# Power_Supply.net
KiCad netlist of a schematic drawn in Altium Designer
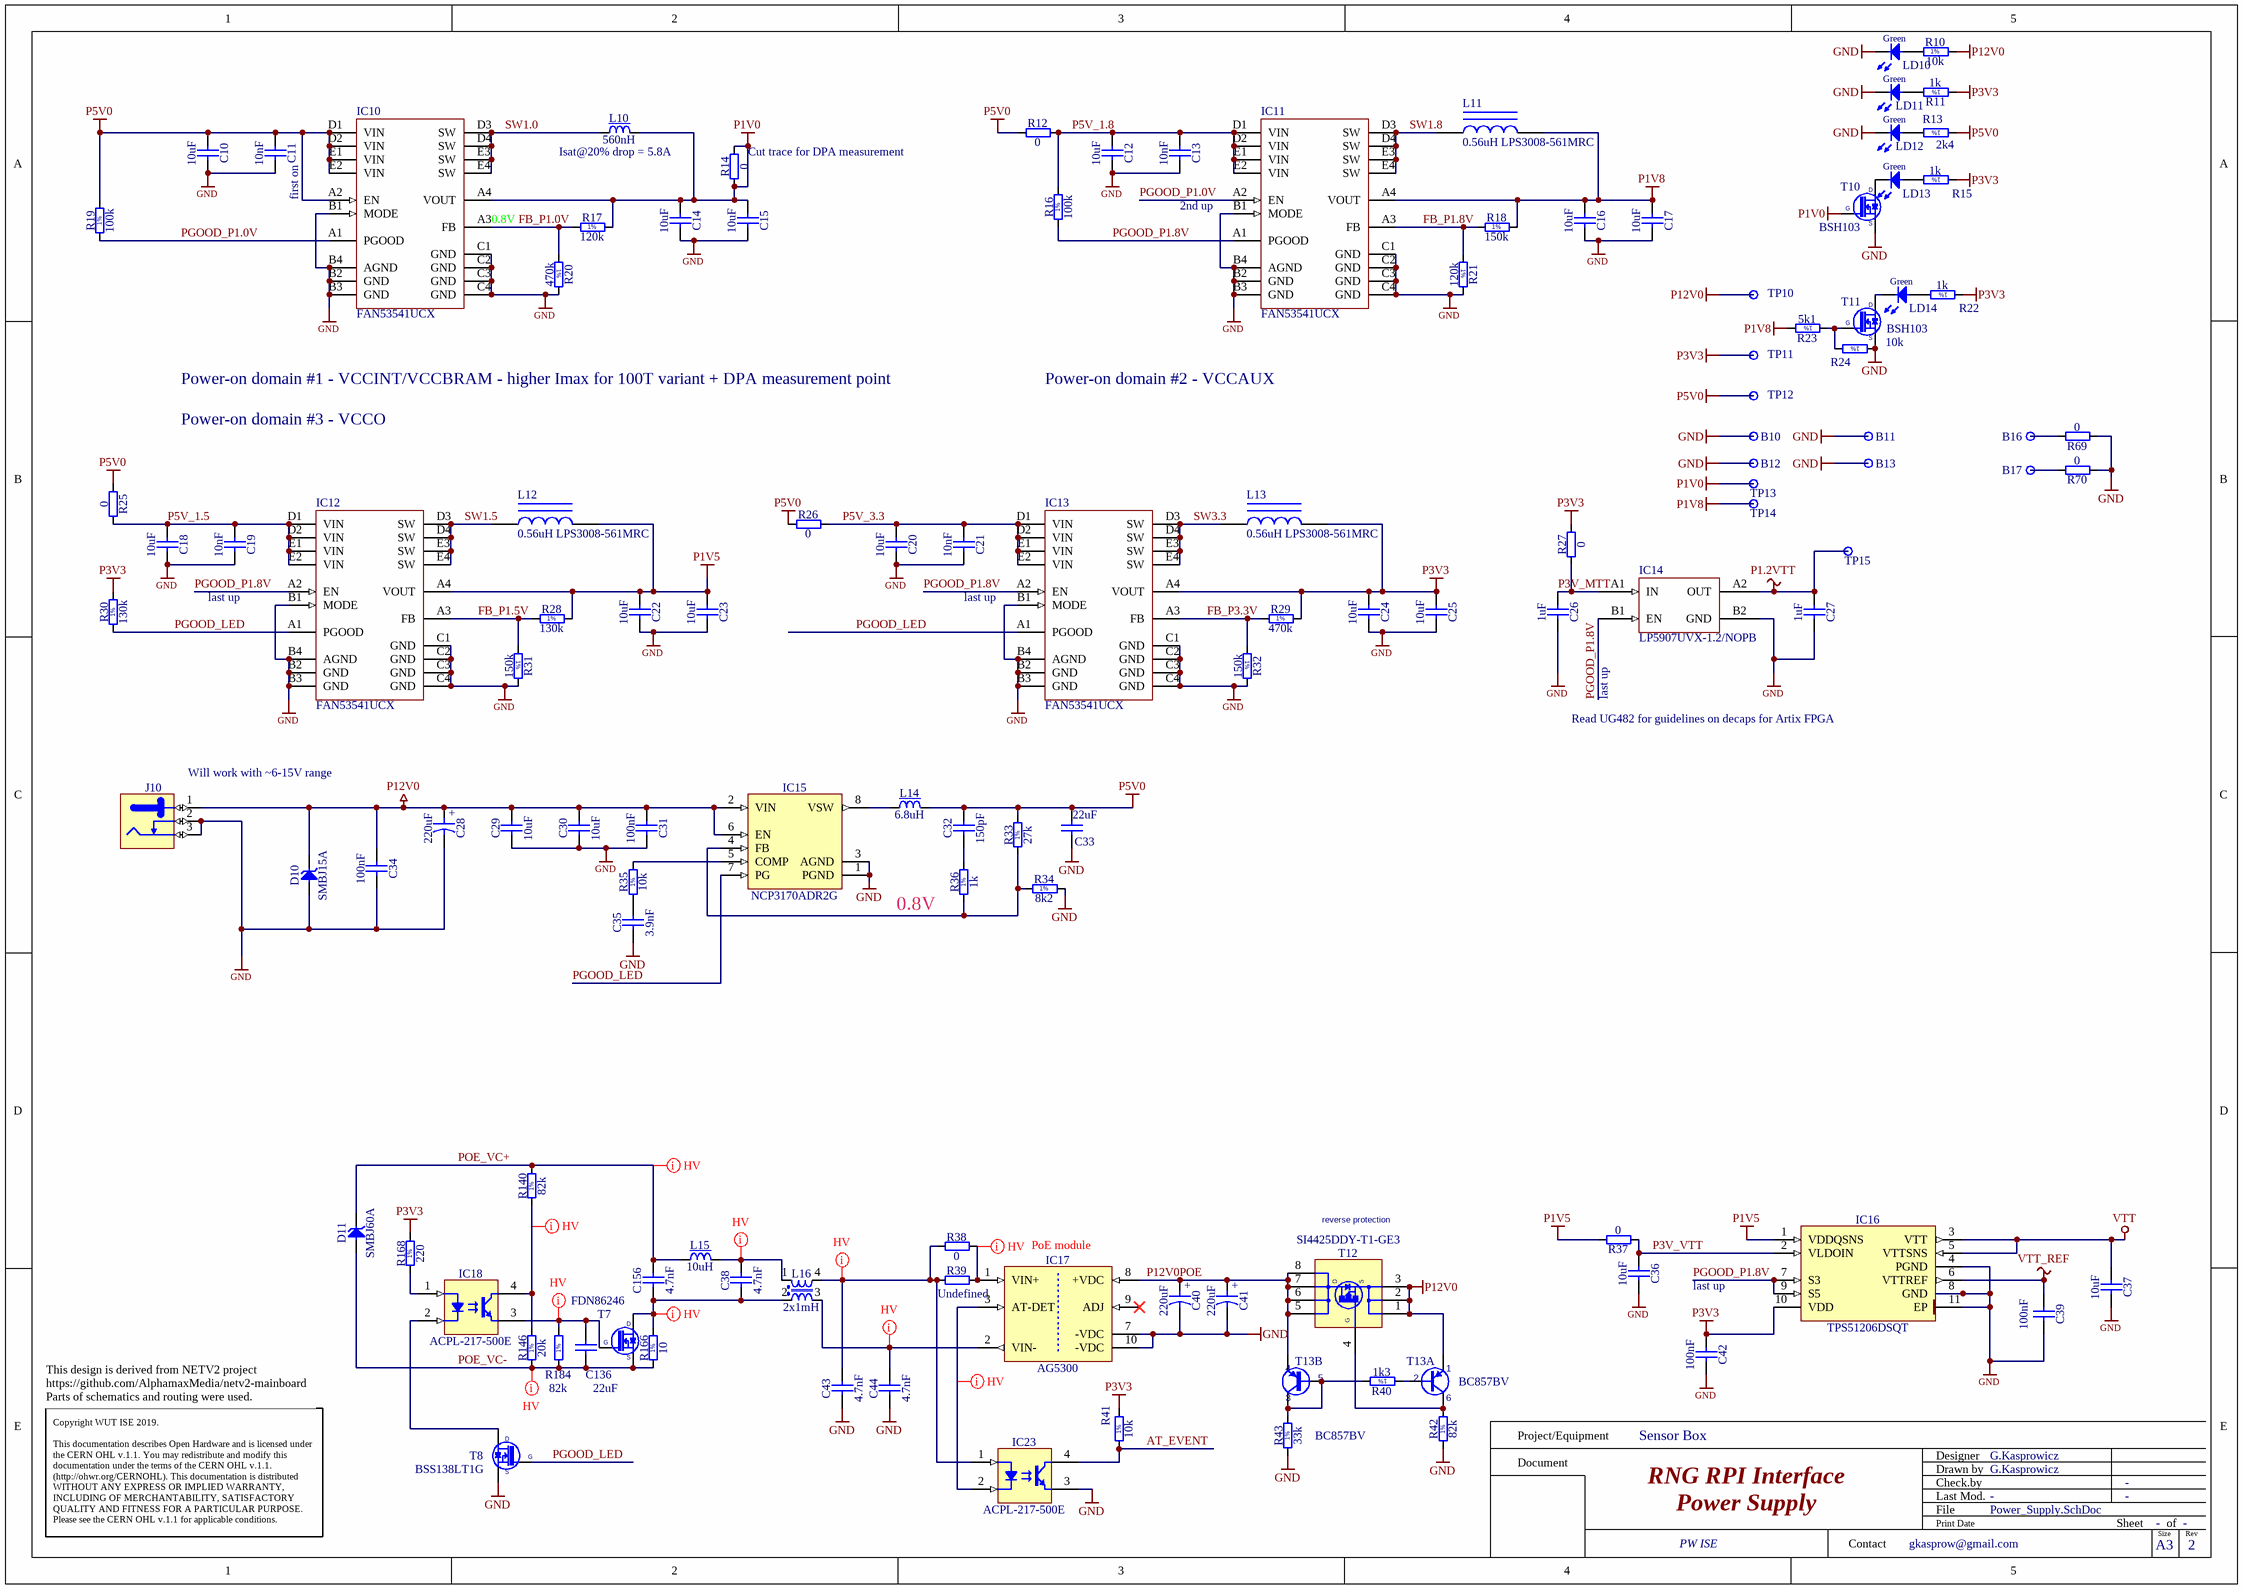
[diagram p0: Power_Supply.SchDoc]

(export (version "E")
  (design (tool "Eeschema 10.0.6"))
  (components
    (comp (ref "B10")
      (value "Plated Hole")
      (footprint "c130h60")
      (description "Single Terminal Socket")
      (fields (field (name "PART NUMBER") "PLATED_HOLE0.6_PAD1.3") (field (name "AUTHOR") "CERN DEM MR"))
      (libsource (lib "Eletro-mechanical") (part "Single Terminal Socket"))
    )
    (comp (ref "B11")
      (value "Plated Hole")
      (footprint "c130h60")
      (description "Single Terminal Socket")
      (fields (field (name "PART NUMBER") "PLATED_HOLE0.6_PAD1.3") (field (name "AUTHOR") "CERN DEM MR"))
      (libsource (lib "Eletro-mechanical") (part "Single Terminal Socket"))
    )
    (comp (ref "B12")
      (value "Plated Hole")
      (footprint "c130h60")
      (description "Single Terminal Socket")
      (fields (field (name "PART NUMBER") "PLATED_HOLE0.6_PAD1.3") (field (name "AUTHOR") "CERN DEM MR"))
      (libsource (lib "Eletro-mechanical") (part "Single Terminal Socket"))
    )
    (comp (ref "B13")
      (value "Plated Hole")
      (footprint "c130h60")
      (description "Single Terminal Socket")
      (fields (field (name "PART NUMBER") "PLATED_HOLE0.6_PAD1.3") (field (name "AUTHOR") "CERN DEM MR"))
      (libsource (lib "Eletro-mechanical") (part "Single Terminal Socket"))
    )
    (comp (ref "B16")
      (value "Plated Hole")
      (footprint "MTG270_500")
      (description "Single Terminal Socket")
      (fields (field (name "PART NUMBER") "PLATED_HOLE2.7_PAD5.0") (field (name "AUTHOR") "CERN DEM JMW"))
      (libsource (lib "Eletro-mechanical") (part "Single Terminal Socket"))
    )
    (comp (ref "B17")
      (value "Plated Hole")
      (footprint "MTG270_500")
      (description "Single Terminal Socket")
      (fields (field (name "PART NUMBER") "PLATED_HOLE2.7_PAD5.0") (field (name "AUTHOR") "CERN DEM JMW"))
      (libsource (lib "Eletro-mechanical") (part "Single Terminal Socket"))
    )
    (comp (ref "C10")
      (value "10uF")
      (footprint "CAPC1608X80N")
      (description "Non-polarised capacitor")
      (fields
        (field (name "PART NUMBER") "CC0603_10UF_10V_10%_X5R")
        (field (name "VOLTAGE") "10V")
        (field (name "AUTHOR") "CERN DEM JLC")
      )
      (libsource (lib "Capacitors") (part "Capacitor - non polarized"))
    )
    (comp (ref "C11")
      (value "10nF")
      (footprint "CAPC1005X55N")
      (description "Non-polarised capacitor")
      (fields
        (field (name "PART NUMBER") "CC0402_10NF_16V_10%_X7R")
        (field (name "VOLTAGE") "16V")
        (field (name "AUTHOR") "CERN DEM JLC")
      )
      (libsource (lib "Capacitors") (part "Capacitor - non polarized"))
    )
    (comp (ref "C12")
      (value "10uF")
      (footprint "CAPC1608X80N")
      (description "Non-polarised capacitor")
      (fields
        (field (name "PART NUMBER") "CC0603_10UF_10V_10%_X5R")
        (field (name "VOLTAGE") "10V")
        (field (name "AUTHOR") "CERN DEM JLC")
      )
      (libsource (lib "Capacitors") (part "Capacitor - non polarized"))
    )
    (comp (ref "C13")
      (value "10nF")
      (footprint "CAPC1005X55N")
      (description "Non-polarised capacitor")
      (fields
        (field (name "PART NUMBER") "CC0402_10NF_16V_10%_X7R")
        (field (name "VOLTAGE") "16V")
        (field (name "AUTHOR") "CERN DEM JLC")
      )
      (libsource (lib "Capacitors") (part "Capacitor - non polarized"))
    )
    (comp (ref "C14")
      (value "10uF")
      (footprint "CAPC1608X80N")
      (description "Non-polarised capacitor")
      (fields
        (field (name "PART NUMBER") "CC0603_10UF_10V_10%_X5R")
        (field (name "VOLTAGE") "10V")
        (field (name "AUTHOR") "CERN DEM JLC")
      )
      (libsource (lib "Capacitors") (part "Capacitor - non polarized"))
    )
    (comp (ref "C15")
      (value "10uF")
      (footprint "CAPC1608X80N")
      (description "Non-polarised capacitor")
      (fields
        (field (name "PART NUMBER") "CC0603_10UF_10V_10%_X5R")
        (field (name "VOLTAGE") "10V")
        (field (name "AUTHOR") "CERN DEM JLC")
      )
      (libsource (lib "Capacitors") (part "Capacitor - non polarized"))
    )
    (comp (ref "C16")
      (value "10uF")
      (footprint "CAPC1608X80N")
      (description "Non-polarised capacitor")
      (fields
        (field (name "PART NUMBER") "CC0603_10UF_10V_10%_X5R")
        (field (name "VOLTAGE") "10V")
        (field (name "AUTHOR") "CERN DEM JLC")
      )
      (libsource (lib "Capacitors") (part "Capacitor - non polarized"))
    )
    (comp (ref "C17")
      (value "10uF")
      (footprint "CAPC1608X80N")
      (description "Non-polarised capacitor")
      (fields
        (field (name "PART NUMBER") "CC0603_10UF_10V_10%_X5R")
        (field (name "VOLTAGE") "10V")
        (field (name "AUTHOR") "CERN DEM JLC")
      )
      (libsource (lib "Capacitors") (part "Capacitor - non polarized"))
    )
    (comp (ref "C18")
      (value "10uF")
      (footprint "CAPC1608X80N")
      (description "Non-polarised capacitor")
      (fields
        (field (name "PART NUMBER") "CC0603_10UF_10V_10%_X5R")
        (field (name "VOLTAGE") "10V")
        (field (name "AUTHOR") "CERN DEM JLC")
      )
      (libsource (lib "Capacitors") (part "Capacitor - non polarized"))
    )
    (comp (ref "C19")
      (value "10nF")
      (footprint "CAPC1005X55N")
      (description "Non-polarised capacitor")
      (fields
        (field (name "PART NUMBER") "CC0402_10NF_16V_10%_X7R")
        (field (name "VOLTAGE") "16V")
        (field (name "AUTHOR") "CERN DEM JLC")
      )
      (libsource (lib "Capacitors") (part "Capacitor - non polarized"))
    )
    (comp (ref "C20")
      (value "10uF")
      (footprint "CAPC1608X80N")
      (description "Non-polarised capacitor")
      (fields
        (field (name "PART NUMBER") "CC0603_10UF_10V_10%_X5R")
        (field (name "VOLTAGE") "10V")
        (field (name "AUTHOR") "CERN DEM JLC")
      )
      (libsource (lib "Capacitors") (part "Capacitor - non polarized"))
    )
    (comp (ref "C21")
      (value "10nF")
      (footprint "CAPC1005X55N")
      (description "Non-polarised capacitor")
      (fields
        (field (name "PART NUMBER") "CC0402_10NF_16V_10%_X7R")
        (field (name "VOLTAGE") "16V")
        (field (name "AUTHOR") "CERN DEM JLC")
      )
      (libsource (lib "Capacitors") (part "Capacitor - non polarized"))
    )
    (comp (ref "C22")
      (value "10uF")
      (footprint "CAPC1608X80N")
      (description "Non-polarised capacitor")
      (fields
        (field (name "PART NUMBER") "CC0603_10UF_10V_10%_X5R")
        (field (name "VOLTAGE") "10V")
        (field (name "AUTHOR") "CERN DEM JLC")
      )
      (libsource (lib "Capacitors") (part "Capacitor - non polarized"))
    )
    (comp (ref "C23")
      (value "10uF")
      (footprint "CAPC1608X80N")
      (description "Non-polarised capacitor")
      (fields
        (field (name "PART NUMBER") "CC0603_10UF_10V_10%_X5R")
        (field (name "VOLTAGE") "10V")
        (field (name "AUTHOR") "CERN DEM JLC")
      )
      (libsource (lib "Capacitors") (part "Capacitor - non polarized"))
    )
    (comp (ref "C24")
      (value "10uF")
      (footprint "CAPC1608X80N")
      (description "Non-polarised capacitor")
      (fields
        (field (name "PART NUMBER") "CC0603_10UF_10V_10%_X5R")
        (field (name "VOLTAGE") "10V")
        (field (name "AUTHOR") "CERN DEM JLC")
      )
      (libsource (lib "Capacitors") (part "Capacitor - non polarized"))
    )
    (comp (ref "C25")
      (value "10uF")
      (footprint "CAPC1608X80N")
      (description "Non-polarised capacitor")
      (fields
        (field (name "PART NUMBER") "CC0603_10UF_10V_10%_X5R")
        (field (name "VOLTAGE") "10V")
        (field (name "AUTHOR") "CERN DEM JLC")
      )
      (libsource (lib "Capacitors") (part "Capacitor - non polarized"))
    )
    (comp (ref "C26")
      (value "1uF")
      (footprint "CAPC1005X55N")
      (description "Non-polarised capacitor")
      (fields
        (field (name "PART NUMBER") "CC0402_1UF_16V_10%_X5R")
        (field (name "VOLTAGE") "16V")
        (field (name "AUTHOR") "CERN DEM JLC")
      )
      (libsource (lib "Capacitors") (part "Capacitor - non polarized"))
    )
    (comp (ref "C27")
      (value "1uF")
      (footprint "CAPC1005X55N")
      (description "Non-polarised capacitor")
      (fields
        (field (name "PART NUMBER") "CC0402_1UF_16V_10%_X5R")
        (field (name "VOLTAGE") "16V")
        (field (name "AUTHOR") "CERN DEM JLC")
      )
      (libsource (lib "Capacitors") (part "Capacitor - non polarized"))
    )
    (comp (ref "C28")
      (value "220uF")
      (footprint "CAPAE830X620N")
      (description "Polarised capacitor")
      (fields
        (field (name "PART NUMBER") "CAE830-620_220UF_16V_20%")
        (field (name "VOLTAGE") "16V")
        (field (name "AUTHOR") "CERN DEM JLC")
      )
      (libsource (lib "Capacitors") (part "Capacitor - polarized"))
    )
    (comp (ref "C29")
      (value "10uF")
      (footprint "CAPC3216X180N")
      (description "Non-polarised capacitor")
      (fields
        (field (name "PART NUMBER") "CC1206_10UF_25V_10%_X7R")
        (field (name "VOLTAGE") "25V")
        (field (name "AUTHOR") "CERN DEM JLC")
      )
      (libsource (lib "Capacitors") (part "Capacitor - non polarized"))
    )
    (comp (ref "C30")
      (value "10uF")
      (footprint "CAPC3216X180N")
      (description "Non-polarised capacitor")
      (fields
        (field (name "PART NUMBER") "CC1206_10UF_25V_10%_X7R")
        (field (name "VOLTAGE") "25V")
        (field (name "AUTHOR") "CERN DEM JLC")
      )
      (libsource (lib "Capacitors") (part "Capacitor - non polarized"))
    )
    (comp (ref "C31")
      (value "100nF")
      (footprint "CAPC2012X135N")
      (description "Non-polarised capacitor")
      (fields
        (field (name "PART NUMBER") "CC0805_100NF_50V_10%_X7R")
        (field (name "VOLTAGE") "50V")
        (field (name "AUTHOR") "CERN DEM JLC")
      )
      (libsource (lib "Capacitors") (part "Capacitor - non polarized"))
    )
    (comp (ref "C32")
      (value "150pF")
      (footprint "CAPC1608X87N")
      (description "Non-polarised capacitor")
      (fields
        (field (name "PART NUMBER") "CC0603_150PF_50V_1%_NP0")
        (field (name "VOLTAGE") "50V")
        (field (name "AUTHOR") "CERN DEM MR")
      )
      (libsource (lib "Capacitors") (part "Capacitor - non polarized"))
    )
    (comp (ref "C33")
      (value "22uF")
      (footprint "CAPC2012X135N")
      (description "Non-polarised capacitor")
      (fields
        (field (name "PART NUMBER") "CC0805_22UF_16V_10%_X5R")
        (field (name "VOLTAGE") "16V")
        (field (name "AUTHOR") "CERN DEM JLC")
      )
      (libsource (lib "Capacitors") (part "Capacitor - non polarized"))
    )
    (comp (ref "C34")
      (value "100nF")
      (footprint "CAPC2012X135N")
      (description "Non-polarised capacitor")
      (fields
        (field (name "PART NUMBER") "CC0805_100NF_50V_10%_X7R")
        (field (name "VOLTAGE") "50V")
        (field (name "AUTHOR") "CERN DEM JLC")
      )
      (libsource (lib "Capacitors") (part "Capacitor - non polarized"))
    )
    (comp (ref "C35")
      (value "3.9nF")
      (footprint "CAPC1608X87N")
      (description "Non-polarised capacitor")
      (fields
        (field (name "PART NUMBER") "CC0603_3.9NF_50V_5%_X7R")
        (field (name "VOLTAGE") "50V")
        (field (name "AUTHOR") "CERN DEM JLC")
      )
      (libsource (lib "Capacitors") (part "Capacitor - non polarized"))
    )
    (comp (ref "C36")
      (value "10uF")
      (footprint "CAPC1608X80N")
      (description "Non-polarised capacitor")
      (fields
        (field (name "PART NUMBER") "CC0603_10UF_10V_10%_X5R")
        (field (name "VOLTAGE") "10V")
        (field (name "AUTHOR") "CERN DEM JLC")
      )
      (libsource (lib "Capacitors") (part "Capacitor - non polarized"))
    )
    (comp (ref "C37")
      (value "10uF")
      (footprint "CAPC1608X80N")
      (description "Non-polarised capacitor")
      (fields
        (field (name "PART NUMBER") "CC0603_10UF_10V_10%_X5R")
        (field (name "VOLTAGE") "10V")
        (field (name "AUTHOR") "CERN DEM JLC")
      )
      (libsource (lib "Capacitors") (part "Capacitor - non polarized"))
    )
    (comp (ref "C38")
      (value "4.7nF")
      (footprint "CAPC3216X140N")
      (description "Non-polarised capacitor")
      (fields
        (field (name "PART NUMBER") "CC1206_4.7NF_500V_10%_X7R")
        (field (name "VOLTAGE") "500V")
        (field (name "AUTHOR") "GK")
      )
      (libsource (lib "LIBRARY_SCH") (part "CAP_SMD_1206_4.7n_500V"))
    )
    (comp (ref "C39")
      (value "100nF")
      (footprint "CAPC0603X33N")
      (description "Non-polarised capacitor")
      (fields
        (field (name "PART NUMBER") "CC0201_100NF_6.3V_10%_X5R")
        (field (name "VOLTAGE") "6.3V")
        (field (name "AUTHOR") "CERN DEM JLC")
      )
      (libsource (lib "Capacitors") (part "Capacitor - non polarized"))
    )
    (comp (ref "C40")
      (value "220uF")
      (footprint "CAPAE830X620N")
      (description "Polarised capacitor")
      (fields
        (field (name "PART NUMBER") "CAE830-620_220UF_16V_20%")
        (field (name "VOLTAGE") "16V")
        (field (name "AUTHOR") "CERN DEM JLC")
      )
      (libsource (lib "Capacitors") (part "Capacitor - polarized"))
    )
    (comp (ref "C41")
      (value "220uF")
      (footprint "CAPAE830X620N")
      (description "Polarised capacitor")
      (fields
        (field (name "PART NUMBER") "CAE830-620_220UF_16V_20%")
        (field (name "VOLTAGE") "16V")
        (field (name "AUTHOR") "CERN DEM JLC")
      )
      (libsource (lib "Capacitors") (part "Capacitor - polarized"))
    )
    (comp (ref "C42")
      (value "100nF")
      (footprint "CAPC0603X33N")
      (description "Non-polarised capacitor")
      (fields
        (field (name "PART NUMBER") "CC0201_100NF_6.3V_10%_X5R")
        (field (name "VOLTAGE") "6.3V")
        (field (name "AUTHOR") "CERN DEM JLC")
      )
      (libsource (lib "Capacitors") (part "Capacitor - non polarized"))
    )
    (comp (ref "C43")
      (value "4.7nF")
      (footprint "CAPC3216X140N")
      (description "Non-polarised capacitor")
      (fields
        (field (name "PART NUMBER") "CC1206_4.7NF_500V_10%_X7R")
        (field (name "VOLTAGE") "500V")
        (field (name "AUTHOR") "GK")
      )
      (libsource (lib "LIBRARY_SCH") (part "CAP_SMD_1206_4.7n_500V"))
    )
    (comp (ref "C44")
      (value "4.7nF")
      (footprint "CAPC3216X140N")
      (description "Non-polarised capacitor")
      (fields
        (field (name "PART NUMBER") "CC1206_4.7NF_500V_10%_X7R")
        (field (name "VOLTAGE") "500V")
        (field (name "AUTHOR") "GK")
      )
      (libsource (lib "LIBRARY_SCH") (part "CAP_SMD_1206_4.7n_500V"))
    )
    (comp (ref "C136")
      (value "22uF")
      (footprint "CAPC2012X135N")
      (description "Non-polarised capacitor")
      (fields
        (field (name "PART NUMBER") "CC0805_22UF_16V_10%_X5R")
        (field (name "VOLTAGE") "16V")
        (field (name "AUTHOR") "CERN DEM JLC")
      )
      (libsource (lib "Capacitors") (part "Capacitor - non polarized"))
    )
    (comp (ref "C156")
      (value "4.7nF")
      (footprint "CAPC3216X140N")
      (description "Non-polarised capacitor")
      (fields
        (field (name "PART NUMBER") "CC1206_4.7NF_500V_10%_X7R")
        (field (name "VOLTAGE") "500V")
        (field (name "AUTHOR") "GK")
      )
      (libsource (lib "LIBRARY_SCH") (part "CAP_SMD_1206_4.7n_500V"))
    )
    (comp (ref "D10")
      (value "SMBJ15A")
      (footprint "DIOM5336X265N")
      (description "Zener Diode")
      (fields
        (field (name "VOLTAGE") "15V")
        (field (name "POWER") "600W")
        (field (name "AUTHOR") "CERN DEM JLC")
      )
      (libsource (lib "ICs And Semiconductors") (part "Diode Zener"))
    )
    (comp (ref "D11")
      (value "SMBJ60A")
      (footprint "DIOM5336X265N")
      (description "Zener Diode")
      (fields
        (field (name "VOLTAGE") "60V")
        (field (name "POWER") "600W")
        (field (name "AUTHOR") "CERN DEM JLC")
      )
      (libsource (lib "ICs And Semiconductors") (part "Diode Zener"))
    )
    (comp (ref "IC10")
      (value "FAN53541UCX")
      (footprint "BGA20C40P4X5_156X196X62")
      (description "2.4MHz, 5A TinyBuck Synchronous Buck Regulator")
      (libsource (lib "commonsch-new") (part "FAN53541UCX"))
    )
    (comp (ref "IC11")
      (value "FAN53541UCX")
      (footprint "BGA20C40P4X5_156X196X62")
      (description "2.4MHz, 5A TinyBuck Synchronous Buck Regulator")
      (libsource (lib "commonsch-new") (part "FAN53541UCX"))
    )
    (comp (ref "IC12")
      (value "FAN53541UCX")
      (footprint "BGA20C40P4X5_156X196X62")
      (description "2.4MHz, 5A TinyBuck Synchronous Buck Regulator")
      (libsource (lib "commonsch-new") (part "FAN53541UCX"))
    )
    (comp (ref "IC13")
      (value "FAN53541UCX")
      (footprint "BGA20C40P4X5_156X196X62")
      (description "2.4MHz, 5A TinyBuck Synchronous Buck Regulator")
      (libsource (lib "commonsch-new") (part "FAN53541UCX"))
    )
    (comp (ref "IC14")
      (value "LP5907UVX-1.2/NOPB")
      (footprint "TI_YKE004")
      (description "Ultra low-noise 250mA LDO for RF and analog in DSBGA")
      (libsource (lib "commonsch-new") (part "LP5907UVX"))
    )
    (comp (ref "IC15")
      (value "NCP3170ADR2G")
      (footprint "SOIC127P600X175-8N")
      (description "Synchronous PWM Switching Converter")
      (fields (field (name "MANUFACTURER") "ON SEMICONDUCTOR") (field (name "AUTHOR") "CERN DEM MR"))
      (libsource (lib "ICs And Semiconductors") (part "NCP3170ADR2G"))
    )
    (comp (ref "IC16")
      (value "TPS51206DSQT")
      (footprint "SON40P200X200X80-11N-R100X160")
      (fields (field (name "MANUFACTURER") "TEXAS INSTRUMENTS") (field (name "AUTHOR") "CERN DEM JLC"))
      (libsource (lib "ICs And Semiconductors") (part "TPS51206"))
    )
    (comp (ref "IC17")
      (value "AG5300")
      (footprint "SILVERTEL_AG5300")
      (description "Power-over-Ethernet Plus (POE+) Module")
      (fields (field (name "MANUFACTURER") "SILVERTEL") (field (name "AUTHOR") "CERN DEM JLC"))
      (libsource (lib "ICs And Semiconductors") (part "AG5300"))
    )
    (comp (ref "IC18")
      (value "ACPL-217-500E")
      (footprint "SOIC127P700X242-4N")
      (description "Single Optocoupler")
      (fields (field (name "MANUFACTURER") "AVAGO TECHNOLOGIES") (field (name "AUTHOR") "CERN DEM JLC"))
      (libsource (lib "ICs And Semiconductors") (part "Optocoupler Type7"))
    )
    (comp (ref "IC23")
      (value "ACPL-217-500E")
      (footprint "SOIC127P700X242-4N")
      (description "Single Optocoupler")
      (fields (field (name "MANUFACTURER") "AVAGO TECHNOLOGIES") (field (name "AUTHOR") "CERN DEM JLC"))
      (libsource (lib "ICs And Semiconductors") (part "Optocoupler Type7"))
    )
    (comp (ref "J10")
      (value "Jack")
      (footprint "CLIFF_FC68148(DC-10A)")
      (description "12V /  5A, 2.1mm Diameter Pin, DC Power Socket With  Switch. DC10A Type")
      (fields
        (field (name "PART NUMBER") "CLIFF_FC68148(DC-10A)")
        (field (name "MANUFACTURER") "CLIFF ELECTRONIC COMPONENTS")
        (field (name "AUTHOR") "CERN DEM JLC")
      )
      (libsource (lib "Connectors") (part "CLIFF_FC68148(DC-10A)"))
    )
    (comp (ref "L10")
      (value "560nH")
      (footprint "IND_COILCRAFT_XAL5020")
      (description "Inductor With Core")
      (fields
        (field (name "PART NUMBER") "IND_560NH_20%_COILCRAFT_XAL5020")
        (field (name "POWER") "9.9A")
        (field (name "AUTHOR") "CERN DEM MR")
      )
      (libsource (lib "Inductors & Transformers") (part "Inductor With Magnetic core"))
    )
    (comp (ref "L11")
      (value "0.56uH LPS3008-561MRC")
      (footprint "COILCRAFT_LPS3008")
      (description "Magnetic-Core Inductor")
      (fields (field (name "MPN") "LPS3008-561MRC"))
      (libsource (lib "Miscellaneous Devices") (part "Inductor Iron"))
    )
    (comp (ref "L12")
      (value "0.56uH LPS3008-561MRC")
      (footprint "COILCRAFT_LPS3008")
      (description "Magnetic-Core Inductor")
      (fields (field (name "MPN") "LPS3008-561MRC"))
      (libsource (lib "Miscellaneous Devices") (part "Inductor Iron"))
    )
    (comp (ref "L13")
      (value "0.56uH LPS3008-561MRC")
      (footprint "COILCRAFT_LPS3008")
      (description "Magnetic-Core Inductor")
      (fields (field (name "MPN") "LPS3008-561MRC"))
      (libsource (lib "Miscellaneous Devices") (part "Inductor Iron"))
    )
    (comp (ref "L14")
      (value "6.8uH")
      (footprint "INDM6965X300N")
      (description "Inductor With Core")
      (fields
        (field (name "PART NUMBER") "IND2525_6.8UH_20%_VISHAY_IHLP-2525CZ-01")
        (field (name "POWER") "4.5A")
        (field (name "AUTHOR") "CERN DEM MR")
      )
      (libsource (lib "Inductors & Transformers") (part "Inductor With Magnetic core"))
    )
    (comp (ref "L15")
      (value "10uH")
      (footprint "IND_MURATA-PS_8400")
      (description "Inductor With Core")
      (fields
        (field (name "PART NUMBER") "IND_10UH_10%_MURATA-PS_8400")
        (field (name "POWER") "950mA")
        (field (name "AUTHOR") "CERN DEM JLC")
      )
      (libsource (lib "Inductors & Transformers") (part "Inductor With Magnetic core"))
    )
    (comp (ref "L16")
      (value "2x1mH")
      (footprint "IND_WURTH_WE-SL2")
      (description "Inductor Common Mode")
      (fields
        (field (name "PART NUMBER") "IND_1MH_50%_WURTH_WE-SL2-744222")
        (field (name "POWER") "800mA")
        (field (name "AUTHOR") "CERN DEM JLC")
      )
      (libsource (lib "Inductors & Transformers") (part "Inductor Common Mode 1Dot-4 2Dot-3"))
    )
    (comp (ref "LD10")
      (value "Green")
      (footprint "LED_KINGBRIGHT_KPH-1608CGCK")
      (description "LED Green 1C 2A")
      (fields
        (field (name "PART NUMBER") "LED_KINGBRIGHT_KPH-1608CGCK")
        (field (name "MANUFACTURER") "KINGBRIGHT")
        (field (name "AUTHOR") "CERN DEM JLC")
      )
      (libsource (lib "ICs And Semiconductors") (part "LED Green 1C 2A"))
    )
    (comp (ref "LD11")
      (value "Green")
      (footprint "LED_KINGBRIGHT_KPH-1608CGCK")
      (description "LED Green 1C 2A")
      (fields
        (field (name "PART NUMBER") "LED_KINGBRIGHT_KPH-1608CGCK")
        (field (name "MANUFACTURER") "KINGBRIGHT")
        (field (name "AUTHOR") "CERN DEM JLC")
      )
      (libsource (lib "ICs And Semiconductors") (part "LED Green 1C 2A"))
    )
    (comp (ref "LD12")
      (value "Green")
      (footprint "LED_KINGBRIGHT_KPH-1608CGCK")
      (description "LED Green 1C 2A")
      (fields
        (field (name "PART NUMBER") "LED_KINGBRIGHT_KPH-1608CGCK")
        (field (name "MANUFACTURER") "KINGBRIGHT")
        (field (name "AUTHOR") "CERN DEM JLC")
      )
      (libsource (lib "ICs And Semiconductors") (part "LED Green 1C 2A"))
    )
    (comp (ref "LD13")
      (value "Green")
      (footprint "LED_KINGBRIGHT_KPH-1608CGCK")
      (description "LED Green 1C 2A")
      (fields
        (field (name "PART NUMBER") "LED_KINGBRIGHT_KPH-1608CGCK")
        (field (name "MANUFACTURER") "KINGBRIGHT")
        (field (name "AUTHOR") "CERN DEM JLC")
      )
      (libsource (lib "ICs And Semiconductors") (part "LED Green 1C 2A"))
    )
    (comp (ref "LD14")
      (value "Green")
      (footprint "LED_KINGBRIGHT_KPH-1608CGCK")
      (description "LED Green 1C 2A")
      (fields
        (field (name "PART NUMBER") "LED_KINGBRIGHT_KPH-1608CGCK")
        (field (name "MANUFACTURER") "KINGBRIGHT")
        (field (name "AUTHOR") "CERN DEM JLC")
      )
      (libsource (lib "ICs And Semiconductors") (part "LED Green 1C 2A"))
    )
    (comp (ref "R10")
      (value "10k")
      (footprint "RESC1005X40N")
      (description "Resistor - 1%")
      (fields
        (field (name "PART NUMBER") "R0402_10K_1%_0.0625W_100PPM")
        (field (name "POWER") "0.0625W")
        (field (name "AUTHOR") "CERN DEM JLC")
      )
      (libsource (lib "Resistors") (part "Resistor - 1%"))
    )
    (comp (ref "R11")
      (value "1k")
      (footprint "RESC1005X40N")
      (description "Resistor - 1%")
      (fields
        (field (name "PART NUMBER") "R0402_1K_1%_0.0625W_100PPM")
        (field (name "POWER") "0.0625W")
        (field (name "AUTHOR") "CERN DEM JLC")
      )
      (libsource (lib "Resistors") (part "Resistor - 1%"))
    )
    (comp (ref "R12")
      (value "0")
      (footprint "RESC1608X55N")
      (description "Resistor")
      (fields
        (field (name "PART NUMBER") "R0603_0R_JUMPER")
        (field (name "MANUFACTURER") "GENERIC")
        (field (name "AUTHOR") "CERN DEM JLC")
      )
      (libsource (lib "Resistors") (part "Resistor"))
    )
    (comp (ref "R13")
      (value "2k4")
      (footprint "RESC1005X40N")
      (description "Resistor - 1%")
      (fields
        (field (name "PART NUMBER") "R0402_2K4_1%_0.0625W_100PPM")
        (field (name "POWER") "0.0625W")
        (field (name "AUTHOR") "CERN DEM JLC")
      )
      (libsource (lib "Resistors") (part "Resistor - 1%"))
    )
    (comp (ref "R14")
      (value "0")
      (footprint "RESC1608X55N")
      (description "Resistor")
      (fields
        (field (name "PART NUMBER") "R0603_0R_JUMPER")
        (field (name "MANUFACTURER") "GENERIC")
        (field (name "AUTHOR") "CERN DEM JLC")
      )
      (libsource (lib "Resistors") (part "Resistor"))
    )
    (comp (ref "R15")
      (value "1k")
      (footprint "RESC1005X40N")
      (description "Resistor - 1%")
      (fields
        (field (name "PART NUMBER") "R0402_1K_1%_0.0625W_100PPM")
        (field (name "POWER") "0.0625W")
        (field (name "AUTHOR") "CERN DEM JLC")
      )
      (libsource (lib "Resistors") (part "Resistor - 1%"))
    )
    (comp (ref "R16")
      (value "100k")
      (footprint "RESC1005X40N")
      (description "Resistor - 1%")
      (fields
        (field (name "PART NUMBER") "R0402_100K_1%_0.0625W_100PPM")
        (field (name "POWER") "0.0625W")
        (field (name "AUTHOR") "CERN DEM JLC")
      )
      (libsource (lib "Resistors") (part "Resistor - 1%"))
    )
    (comp (ref "R17")
      (value "120k")
      (footprint "RESC1005X40N")
      (description "Resistor - 1%")
      (fields
        (field (name "PART NUMBER") "R0402_120K_1%_0.0625W_100PPM")
        (field (name "POWER") "0.0625W")
        (field (name "AUTHOR") "CERN DEM JLC")
      )
      (libsource (lib "Resistors") (part "Resistor - 1%"))
    )
    (comp (ref "R18")
      (value "150k")
      (footprint "RESC1005X40N")
      (description "Resistor - 1%")
      (fields
        (field (name "PART NUMBER") "R0402_150K_1%_0.0625W_100PPM")
        (field (name "POWER") "0.0625W")
        (field (name "AUTHOR") "CERN DEM JLC")
      )
      (libsource (lib "Resistors") (part "Resistor - 1%"))
    )
    (comp (ref "R19")
      (value "100k")
      (footprint "RESC1005X40N")
      (description "Resistor - 1%")
      (fields
        (field (name "PART NUMBER") "R0402_100K_1%_0.0625W_100PPM")
        (field (name "POWER") "0.0625W")
        (field (name "AUTHOR") "CERN DEM JLC")
      )
      (libsource (lib "Resistors") (part "Resistor - 1%"))
    )
    (comp (ref "R20")
      (value "470k")
      (footprint "RESC1005X40N")
      (description "Resistor - 1%")
      (fields
        (field (name "PART NUMBER") "R0402_470K_1%_0.0625W_100PPM")
        (field (name "POWER") "0.0625W")
        (field (name "AUTHOR") "CERN DEM JLC")
      )
      (libsource (lib "Resistors") (part "Resistor - 1%"))
    )
    (comp (ref "R21")
      (value "120k")
      (footprint "RESC1005X40N")
      (description "Resistor - 1%")
      (fields
        (field (name "PART NUMBER") "R0402_120K_1%_0.0625W_100PPM")
        (field (name "POWER") "0.0625W")
        (field (name "AUTHOR") "CERN DEM JLC")
      )
      (libsource (lib "Resistors") (part "Resistor - 1%"))
    )
    (comp (ref "R22")
      (value "1k")
      (footprint "RESC1005X40N")
      (description "Resistor - 1%")
      (fields
        (field (name "PART NUMBER") "R0402_1K_1%_0.0625W_100PPM")
        (field (name "POWER") "0.0625W")
        (field (name "AUTHOR") "CERN DEM JLC")
      )
      (libsource (lib "Resistors") (part "Resistor - 1%"))
    )
    (comp (ref "R23")
      (value "5k1")
      (footprint "RESC1005X40N")
      (description "Resistor - 1%")
      (fields
        (field (name "PART NUMBER") "R0402_5K1_1%_0.0625W_100PPM")
        (field (name "POWER") "0.0625W")
        (field (name "AUTHOR") "CERN DEM JLC")
      )
      (libsource (lib "Resistors") (part "Resistor - 1%"))
    )
    (comp (ref "R24")
      (value "10k")
      (footprint "RESC1005X40N")
      (description "Resistor - 1%")
      (fields
        (field (name "PART NUMBER") "R0402_10K_1%_0.0625W_100PPM")
        (field (name "POWER") "0.0625W")
        (field (name "AUTHOR") "CERN DEM JLC")
      )
      (libsource (lib "Resistors") (part "Resistor - 1%"))
    )
    (comp (ref "R25")
      (value "0")
      (footprint "RESC1608X55N")
      (description "Resistor")
      (fields
        (field (name "PART NUMBER") "R0603_0R_JUMPER")
        (field (name "MANUFACTURER") "GENERIC")
        (field (name "AUTHOR") "CERN DEM JLC")
      )
      (libsource (lib "Resistors") (part "Resistor"))
    )
    (comp (ref "R26")
      (value "0")
      (footprint "RESC1608X55N")
      (description "Resistor")
      (fields
        (field (name "PART NUMBER") "R0603_0R_JUMPER")
        (field (name "MANUFACTURER") "GENERIC")
        (field (name "AUTHOR") "CERN DEM JLC")
      )
      (libsource (lib "Resistors") (part "Resistor"))
    )
    (comp (ref "R27")
      (value "0")
      (footprint "RESC1608X55N")
      (description "Resistor")
      (fields
        (field (name "PART NUMBER") "R0603_0R_JUMPER")
        (field (name "MANUFACTURER") "GENERIC")
        (field (name "AUTHOR") "CERN DEM JLC")
      )
      (libsource (lib "Resistors") (part "Resistor"))
    )
    (comp (ref "R28")
      (value "130k")
      (footprint "RESC1005X40N")
      (description "Resistor - 1%")
      (fields
        (field (name "PART NUMBER") "R0402_130K_1%_0.0625W_100PPM")
        (field (name "POWER") "0.0625W")
        (field (name "AUTHOR") "CERN DEM JLC")
      )
      (libsource (lib "Resistors") (part "Resistor - 1%"))
    )
    (comp (ref "R29")
      (value "470k")
      (footprint "RESC1005X40N")
      (description "Resistor - 1%")
      (fields
        (field (name "PART NUMBER") "R0402_470K_1%_0.0625W_100PPM")
        (field (name "POWER") "0.0625W")
        (field (name "AUTHOR") "CERN DEM JLC")
      )
      (libsource (lib "Resistors") (part "Resistor - 1%"))
    )
    (comp (ref "R30")
      (value "130k")
      (footprint "RESC1005X40N")
      (description "Resistor - 1%")
      (fields
        (field (name "PART NUMBER") "R0402_130K_1%_0.0625W_100PPM")
        (field (name "POWER") "0.0625W")
        (field (name "AUTHOR") "CERN DEM JLC")
      )
      (libsource (lib "Resistors") (part "Resistor - 1%"))
    )
    (comp (ref "R31")
      (value "150k")
      (footprint "RESC1005X40N")
      (description "Resistor - 1%")
      (fields
        (field (name "PART NUMBER") "R0402_150K_1%_0.0625W_100PPM")
        (field (name "POWER") "0.0625W")
        (field (name "AUTHOR") "CERN DEM JLC")
      )
      (libsource (lib "Resistors") (part "Resistor - 1%"))
    )
    (comp (ref "R32")
      (value "150k")
      (footprint "RESC1005X40N")
      (description "Resistor - 1%")
      (fields
        (field (name "PART NUMBER") "R0402_150K_1%_0.0625W_100PPM")
        (field (name "POWER") "0.0625W")
        (field (name "AUTHOR") "CERN DEM JLC")
      )
      (libsource (lib "Resistors") (part "Resistor - 1%"))
    )
    (comp (ref "R33")
      (value "27k")
      (footprint "RESC1005X40N")
      (description "Resistor - 1%")
      (fields
        (field (name "PART NUMBER") "R0402_27K_1%_0.0625W_100PPM")
        (field (name "POWER") "0.0625W")
        (field (name "AUTHOR") "CERN DEM JLC")
      )
      (libsource (lib "Resistors") (part "Resistor - 1%"))
    )
    (comp (ref "R34")
      (value "8k2")
      (footprint "RESC1005X40N")
      (description "Resistor - 1%")
      (fields
        (field (name "PART NUMBER") "R0402_8K2_1%_0.0625W_100PPM")
        (field (name "POWER") "0.0625W")
        (field (name "AUTHOR") "CERN DEM JLC")
      )
      (libsource (lib "Resistors") (part "Resistor - 1%"))
    )
    (comp (ref "R35")
      (value "10k")
      (footprint "RESC1005X40N")
      (description "Resistor - 1%")
      (fields
        (field (name "PART NUMBER") "R0402_10K_1%_0.0625W_100PPM")
        (field (name "POWER") "0.0625W")
        (field (name "AUTHOR") "CERN DEM JLC")
      )
      (libsource (lib "Resistors") (part "Resistor - 1%"))
    )
    (comp (ref "R36")
      (value "1k")
      (footprint "RESC1005X40N")
      (description "Resistor - 1%")
      (fields
        (field (name "PART NUMBER") "R0402_1K_1%_0.0625W_100PPM")
        (field (name "POWER") "0.0625W")
        (field (name "AUTHOR") "CERN DEM JLC")
      )
      (libsource (lib "Resistors") (part "Resistor - 1%"))
    )
    (comp (ref "R37")
      (value "0")
      (footprint "RESC1608X55N")
      (description "Resistor")
      (fields
        (field (name "PART NUMBER") "R0603_0R_JUMPER")
        (field (name "MANUFACTURER") "GENERIC")
        (field (name "AUTHOR") "CERN DEM JLC")
      )
      (libsource (lib "Resistors") (part "Resistor"))
    )
    (comp (ref "R38")
      (value "0")
      (footprint "RESC1005X40N")
      (description "Resistor")
      (fields
        (field (name "PART NUMBER") "R0402_0R_JUMPER")
        (field (name "MANUFACTURER") "GENERIC")
        (field (name "AUTHOR") "CERN DEM JLC")
      )
      (libsource (lib "Resistors") (part "Resistor"))
    )
    (comp (ref "R39")
      (value "Undefined")
      (footprint "RESC2012X60N")
      (description "Resistor")
      (fields (field (name "PART NUMBER") "R0805_NO-VALUE") (field (name "AUTHOR") "CERN DEM JLC"))
      (libsource (lib "Resistors") (part "Resistor"))
    )
    (comp (ref "R40")
      (value "1k3")
      (footprint "RESC1608X55N")
      (description "Resistor - 1%")
      (fields
        (field (name "PART NUMBER") "R0603_1K3_1%_0.1W_100PPM")
        (field (name "POWER") "0.1W")
        (field (name "AUTHOR") "CERN DEM JLC")
      )
      (libsource (lib "Resistors") (part "Resistor - 1%"))
    )
    (comp (ref "R41")
      (value "10k")
      (footprint "RESC1005X40N")
      (description "Resistor - 1%")
      (fields
        (field (name "PART NUMBER") "R0402_10K_1%_0.0625W_100PPM")
        (field (name "POWER") "0.0625W")
        (field (name "AUTHOR") "CERN DEM JLC")
      )
      (libsource (lib "Resistors") (part "Resistor - 1%"))
    )
    (comp (ref "R42")
      (value "82k")
      (footprint "RESC1608X55N")
      (description "Resistor - 1%")
      (fields
        (field (name "PART NUMBER") "R0603_82K_1%_0.1W_100PPM")
        (field (name "POWER") "0.1W")
        (field (name "AUTHOR") "CERN DEM JLC")
      )
      (libsource (lib "Resistors") (part "Resistor - 1%"))
    )
    (comp (ref "R43")
      (value "33k")
      (footprint "RESC1005X40N")
      (description "Resistor - 1%")
      (fields
        (field (name "PART NUMBER") "R0402_33K_1%_0.0625W_100PPM")
        (field (name "POWER") "0.0625W")
        (field (name "AUTHOR") "CERN DEM JLC")
      )
      (libsource (lib "Resistors") (part "Resistor - 1%"))
    )
    (comp (ref "R69")
      (value "0")
      (footprint "RESC1608X55N")
      (description "Resistor")
      (fields
        (field (name "PART NUMBER") "R0603_0R_JUMPER")
        (field (name "MANUFACTURER") "GENERIC")
        (field (name "AUTHOR") "CERN DEM JLC")
      )
      (libsource (lib "Resistors") (part "Resistor"))
    )
    (comp (ref "R70")
      (value "0")
      (footprint "RESC1608X55N")
      (description "Resistor")
      (fields
        (field (name "PART NUMBER") "R0603_0R_JUMPER")
        (field (name "MANUFACTURER") "GENERIC")
        (field (name "AUTHOR") "CERN DEM JLC")
      )
      (libsource (lib "Resistors") (part "Resistor"))
    )
    (comp (ref "R140")
      (value "82k")
      (footprint "RESC1608X55N")
      (description "Resistor - 1%")
      (fields
        (field (name "PART NUMBER") "R0603_82K_1%_0.1W_100PPM")
        (field (name "POWER") "0.1W")
        (field (name "AUTHOR") "CERN DEM JLC")
      )
      (libsource (lib "Resistors") (part "Resistor - 1%"))
    )
    (comp (ref "R146")
      (value "20k")
      (footprint "RESC1005X40N")
      (description "Resistor - 1%")
      (fields
        (field (name "PART NUMBER") "R0402_20K_1%_0.0625W_100PPM")
        (field (name "POWER") "0.0625W")
        (field (name "AUTHOR") "CERN DEM JLC")
      )
      (libsource (lib "Resistors") (part "Resistor - 1%"))
    )
    (comp (ref "R166")
      (value "10")
      (footprint "RESC2012X60N")
      (description "Resistor - 1%")
      (fields
        (field (name "PART NUMBER") "R0805_10R_1%_0.125W_200PPM")
        (field (name "POWER") "0.125W")
        (field (name "AUTHOR") "CERN DEM JLC")
      )
      (libsource (lib "Resistors") (part "Resistor - 1%"))
    )
    (comp (ref "R168")
      (value "220")
      (footprint "RESC1608X55N")
      (description "Resistor - 1%")
      (fields
        (field (name "PART NUMBER") "R0603_220R_1%_0.1W_100PPM")
        (field (name "POWER") "0.1W")
        (field (name "AUTHOR") "CERN DEM JLC")
      )
      (libsource (lib "Resistors") (part "Resistor - 1%"))
    )
    (comp (ref "R184")
      (value "82k")
      (footprint "RESC1608X55N")
      (description "Resistor - 1%")
      (fields
        (field (name "PART NUMBER") "R0603_82K_1%_0.1W_100PPM")
        (field (name "POWER") "0.1W")
        (field (name "AUTHOR") "CERN DEM JLC")
      )
      (libsource (lib "Resistors") (part "Resistor - 1%"))
    )
    (comp (ref "T7")
      (value "FDN86246")
      (footprint "SOT95P237X112-3N")
      (description "N-CHANNEL MOSFET WITH DIODE")
      (fields (field (name "MANUFACTURER") "ON SEMICONDUCTOR") (field (name "AUTHOR") "CERN DEM BC"))
      (libsource (lib "ICs And Semiconductors") (part "N-MOSFET-D 1G 2S 3D"))
    )
    (comp (ref "T8")
      (value "BSS138LT1G")
      (footprint "SOT95P240X110-3N")
      (description "N-CHANNEL MOSFET WITH DIODE")
      (fields (field (name "MANUFACTURER") "ON SEMICONDUCTOR") (field (name "AUTHOR") "CERN DEM JLC"))
      (libsource (lib "") (part "N-MOSFET-D 1G 2S 3D_1"))
    )
    (comp (ref "T10")
      (value "BSH103")
      (footprint "SOT95P230X110-3N")
      (description "N-CHANNEL MOSFET WITH DIODE")
      (fields (field (name "MANUFACTURER") "NEXPERIA") (field (name "AUTHOR") "CERN DEM JLC"))
      (libsource (lib "ICs And Semiconductors") (part "N-MOSFET-D 1G 2S 3D"))
    )
    (comp (ref "T11")
      (value "BSH103")
      (footprint "SOT95P230X110-3N")
      (description "N-CHANNEL MOSFET WITH DIODE")
      (fields (field (name "MANUFACTURER") "NEXPERIA") (field (name "AUTHOR") "CERN DEM JLC"))
      (libsource (lib "ICs And Semiconductors") (part "N-MOSFET-D 1G 2S 3D"))
    )
    (comp (ref "T12")
      (value "SI4425DDY-T1-GE3")
      (footprint "SOIC127P600X175-8N")
      (description "-30V -19.7A P-Channel MOSFET")
      (fields (field (name "MANUFACTURER") "VISHAY SILICONIX") (field (name "AUTHOR") "CERN DEM MR"))
      (libsource (lib "ICs And Semiconductors") (part "SI4425DDY"))
    )
    (comp (ref "T13")
      (value "BC857BV")
      (footprint "SOTFL50P160X60-6N")
      (description "45V, 100mA PNP General Purpose Double Transistor")
      (fields (field (name "MANUFACTURER") "NXP SEMICONDUCTORS") (field (name "AUTHOR") "CERN DEM JLC"))
      (libsource (lib "") (part "BC857BV_1"))
    )
    (comp (ref "TP10")
      (value "Test Point")
      (footprint "TPS127")
      (fields (field (name "PART NUMBER") "SMD_PAD_1.27X1.27MM") (field (name "AUTHOR") "CERN DEM JLC"))
      (libsource (lib "Eletro-mechanical") (part "Test Point"))
    )
    (comp (ref "TP11")
      (value "Test Point")
      (footprint "TPS127")
      (fields (field (name "PART NUMBER") "SMD_PAD_1.27X1.27MM") (field (name "AUTHOR") "CERN DEM JLC"))
      (libsource (lib "Eletro-mechanical") (part "Test Point"))
    )
    (comp (ref "TP12")
      (value "Test Point")
      (footprint "TPS127")
      (fields (field (name "PART NUMBER") "SMD_PAD_1.27X1.27MM") (field (name "AUTHOR") "CERN DEM JLC"))
      (libsource (lib "Eletro-mechanical") (part "Test Point"))
    )
    (comp (ref "TP13")
      (value "Test Point")
      (footprint "TPS127")
      (fields (field (name "PART NUMBER") "SMD_PAD_1.27X1.27MM") (field (name "AUTHOR") "CERN DEM JLC"))
      (libsource (lib "Eletro-mechanical") (part "Test Point"))
    )
    (comp (ref "TP14")
      (value "Test Point")
      (footprint "TPS127")
      (fields (field (name "PART NUMBER") "SMD_PAD_1.27X1.27MM") (field (name "AUTHOR") "CERN DEM JLC"))
      (libsource (lib "Eletro-mechanical") (part "Test Point"))
    )
    (comp (ref "TP15")
      (value "Test Point")
      (footprint "TPS127")
      (fields (field (name "PART NUMBER") "SMD_PAD_1.27X1.27MM") (field (name "AUTHOR") "CERN DEM JLC"))
      (libsource (lib "Eletro-mechanical") (part "Test Point"))
    )
  )
  (nets
    (net (code "1") (name "/AT_EVENT") (class "Default")
      (node (ref "IC23") (pin "4") (pinfunction "C_4") (pintype "open_collector"))
      (node (ref "R41") (pin "1") (pinfunction "1_1") (pintype "passive"))
    )
    (net (code "2") (name "/FB_P1.0V") (class "Default")
      (node (ref "IC10") (pin "A3") (pinfunction "FB_A3") (pintype "passive"))
      (node (ref "R17") (pin "1") (pinfunction "1_1") (pintype "passive"))
      (node (ref "R20") (pin "1") (pinfunction "1_1") (pintype "passive"))
    )
    (net (code "3") (name "/FB_P1.5V") (class "Default")
      (node (ref "IC12") (pin "A3") (pinfunction "FB_A3") (pintype "passive"))
      (node (ref "R28") (pin "1") (pinfunction "1_1") (pintype "passive"))
      (node (ref "R31") (pin "1") (pinfunction "1_1") (pintype "passive"))
    )
    (net (code "4") (name "/FB_P1.8V") (class "Default")
      (node (ref "IC11") (pin "A3") (pinfunction "FB_A3") (pintype "passive"))
      (node (ref "R18") (pin "1") (pinfunction "1_1") (pintype "passive"))
      (node (ref "R21") (pin "1") (pinfunction "1_1") (pintype "passive"))
    )
    (net (code "5") (name "/FB_P3.3V") (class "Default")
      (node (ref "IC13") (pin "A3") (pinfunction "FB_A3") (pintype "passive"))
      (node (ref "R29") (pin "1") (pinfunction "1_1") (pintype "passive"))
      (node (ref "R32") (pin "1") (pinfunction "1_1") (pintype "passive"))
    )
    (net (code "6") (name "/P3V_MTT") (class "Default")
      (node (ref "C26") (pin "1") (pinfunction "1_1") (pintype "passive"))
      (node (ref "IC14") (pin "A1") (pinfunction "IN_A1") (pintype "input"))
      (node (ref "R27") (pin "1") (pinfunction "1_1") (pintype "passive"))
    )
    (net (code "7") (name "/P3V_VTT") (class "Default")
      (node (ref "C36") (pin "1") (pinfunction "1_1") (pintype "passive"))
      (node (ref "IC16") (pin "2") (pinfunction "VLDOIN_2") (pintype "input"))
      (node (ref "R37") (pin "1") (pinfunction "1_1") (pintype "passive"))
    )
    (net (code "8") (name "/P5V_1.5") (class "Default")
      (node (ref "C18") (pin "1") (pinfunction "1_1") (pintype "passive"))
      (node (ref "C19") (pin "1") (pinfunction "1_1") (pintype "passive"))
      (node (ref "IC12") (pin "D1") (pinfunction "VIN_D1") (pintype "power_in"))
      (node (ref "IC12") (pin "D2") (pinfunction "VIN_D2") (pintype "power_in"))
      (node (ref "IC12") (pin "E1") (pinfunction "VIN_E1") (pintype "power_in"))
      (node (ref "IC12") (pin "E2") (pinfunction "VIN_E2") (pintype "power_in"))
      (node (ref "R25") (pin "2") (pinfunction "2_2") (pintype "passive"))
    )
    (net (code "9") (name "/P5V_1.8") (class "Default")
      (node (ref "C12") (pin "1") (pinfunction "1_1") (pintype "passive"))
      (node (ref "C13") (pin "1") (pinfunction "1_1") (pintype "passive"))
      (node (ref "IC11") (pin "D1") (pinfunction "VIN_D1") (pintype "power_in"))
      (node (ref "IC11") (pin "D2") (pinfunction "VIN_D2") (pintype "power_in"))
      (node (ref "IC11") (pin "E1") (pinfunction "VIN_E1") (pintype "power_in"))
      (node (ref "IC11") (pin "E2") (pinfunction "VIN_E2") (pintype "power_in"))
      (node (ref "R12") (pin "2") (pinfunction "2_2") (pintype "passive"))
      (node (ref "R16") (pin "2") (pinfunction "2_2") (pintype "passive"))
    )
    (net (code "10") (name "/P5V_3.3") (class "Default")
      (node (ref "C20") (pin "1") (pinfunction "1_1") (pintype "passive"))
      (node (ref "C21") (pin "1") (pinfunction "1_1") (pintype "passive"))
      (node (ref "IC13") (pin "D1") (pinfunction "VIN_D1") (pintype "power_in"))
      (node (ref "IC13") (pin "D2") (pinfunction "VIN_D2") (pintype "power_in"))
      (node (ref "IC13") (pin "E1") (pinfunction "VIN_E1") (pintype "power_in"))
      (node (ref "IC13") (pin "E2") (pinfunction "VIN_E2") (pintype "power_in"))
      (node (ref "R26") (pin "2") (pinfunction "2_2") (pintype "passive"))
    )
    (net (code "11") (name "/P12V0POE") (class "Default")
      (node (ref "C40") (pin "1") (pinfunction "1_1") (pintype "passive"))
      (node (ref "C41") (pin "1") (pinfunction "1_1") (pintype "passive"))
      (node (ref "IC17") (pin "8") (pinfunction "+VDC_8") (pintype "input"))
      (node (ref "T12") (pin "5") (pinfunction "D_5") (pintype "passive"))
      (node (ref "T12") (pin "6") (pinfunction "D_6") (pintype "passive"))
      (node (ref "T12") (pin "7") (pinfunction "D_7") (pintype "passive"))
      (node (ref "T12") (pin "8") (pinfunction "D_8") (pintype "passive"))
      (node (ref "T13") (pin "4") (pinfunction "E_4") (pintype "passive"))
    )
    (net (code "12") (name "/PGOOD_LED") (class "Default")
      (node (ref "IC12") (pin "A1") (pinfunction "PGOOD_A1") (pintype "open_collector"))
      (node (ref "IC13") (pin "A1") (pinfunction "PGOOD_A1") (pintype "open_collector"))
      (node (ref "IC15") (pin "7") (pinfunction "PG_7") (pintype "input"))
      (node (ref "R30") (pin "1") (pinfunction "1_1") (pintype "passive"))
      (node (ref "T8") (pin "1") (pinfunction "G_1") (pintype "passive"))
    )
    (net (code "13") (name "/PGOOD_P1.0V") (class "Default")
      (node (ref "IC10") (pin "A1") (pinfunction "PGOOD_A1") (pintype "open_collector"))
      (node (ref "IC11") (pin "A2") (pinfunction "EN_A2") (pintype "input"))
      (node (ref "R19") (pin "1") (pinfunction "1_1") (pintype "passive"))
    )
    (net (code "14") (name "/PGOOD_P1.8V") (class "Default")
      (node (ref "IC11") (pin "A1") (pinfunction "PGOOD_A1") (pintype "open_collector"))
      (node (ref "IC12") (pin "A2") (pinfunction "EN_A2") (pintype "input"))
      (node (ref "IC13") (pin "A2") (pinfunction "EN_A2") (pintype "input"))
      (node (ref "IC14") (pin "B1") (pinfunction "EN_B1") (pintype "input"))
      (node (ref "IC16") (pin "7") (pinfunction "S3_7") (pintype "input"))
      (node (ref "IC16") (pin "9") (pinfunction "S5_9") (pintype "input"))
      (node (ref "R16") (pin "1") (pinfunction "1_1") (pintype "passive"))
    )
    (net (code "15") (name "/POE_VC+") (class "Default")
      (node (ref "C156") (pin "2") (pinfunction "2_2") (pintype "passive"))
      (node (ref "D11") (pin "1") (pinfunction "C_1") (pintype "passive"))
      (node (ref "L15") (pin "1") (pinfunction "1_1") (pintype "passive"))
      (node (ref "R140") (pin "2") (pinfunction "2_2") (pintype "passive"))
    )
    (net (code "16") (name "/POE_VC-") (class "Default")
      (node (ref "C136") (pin "1") (pinfunction "1_1") (pintype "passive"))
      (node (ref "D11") (pin "2") (pinfunction "A_2") (pintype "passive"))
      (node (ref "R146") (pin "1") (pinfunction "1_1") (pintype "passive"))
      (node (ref "R166") (pin "1") (pinfunction "1_1") (pintype "passive"))
      (node (ref "R184") (pin "1") (pinfunction "1_1") (pintype "passive"))
      (node (ref "T7") (pin "2") (pinfunction "S_2") (pintype "passive"))
    )
    (net (code "17") (name "/SW1.0") (class "Default")
      (node (ref "IC10") (pin "D3") (pinfunction "SW_D3") (pintype "power_in"))
      (node (ref "IC10") (pin "D4") (pinfunction "SW_D4") (pintype "power_in"))
      (node (ref "IC10") (pin "E3") (pinfunction "SW_E3") (pintype "power_in"))
      (node (ref "IC10") (pin "E4") (pinfunction "SW_E4") (pintype "power_in"))
      (node (ref "L10") (pin "1") (pinfunction "1_1") (pintype "passive"))
    )
    (net (code "18") (name "/SW1.5") (class "Default")
      (node (ref "IC12") (pin "D3") (pinfunction "SW_D3") (pintype "power_in"))
      (node (ref "IC12") (pin "D4") (pinfunction "SW_D4") (pintype "power_in"))
      (node (ref "IC12") (pin "E3") (pinfunction "SW_E3") (pintype "power_in"))
      (node (ref "IC12") (pin "E4") (pinfunction "SW_E4") (pintype "power_in"))
      (node (ref "L12") (pin "1") (pinfunction "1_1") (pintype "passive"))
    )
    (net (code "19") (name "/SW1.8") (class "Default")
      (node (ref "IC11") (pin "D3") (pinfunction "SW_D3") (pintype "power_in"))
      (node (ref "IC11") (pin "D4") (pinfunction "SW_D4") (pintype "power_in"))
      (node (ref "IC11") (pin "E3") (pinfunction "SW_E3") (pintype "power_in"))
      (node (ref "IC11") (pin "E4") (pinfunction "SW_E4") (pintype "power_in"))
      (node (ref "L11") (pin "1") (pinfunction "1_1") (pintype "passive"))
    )
    (net (code "20") (name "/SW3.3") (class "Default")
      (node (ref "IC13") (pin "D3") (pinfunction "SW_D3") (pintype "power_in"))
      (node (ref "IC13") (pin "D4") (pinfunction "SW_D4") (pintype "power_in"))
      (node (ref "IC13") (pin "E3") (pinfunction "SW_E3") (pintype "power_in"))
      (node (ref "IC13") (pin "E4") (pinfunction "SW_E4") (pintype "power_in"))
      (node (ref "L13") (pin "1") (pinfunction "1_1") (pintype "passive"))
    )
    (net (code "21") (name "GND") (class "Default")
      (node (ref "B10") (pin "1") (pinfunction "1_1") (pintype "bidirectional"))
      (node (ref "B11") (pin "1") (pinfunction "1_1") (pintype "bidirectional"))
      (node (ref "B12") (pin "1") (pinfunction "1_1") (pintype "bidirectional"))
      (node (ref "B13") (pin "1") (pinfunction "1_1") (pintype "bidirectional"))
      (node (ref "C10") (pin "2") (pinfunction "2_2") (pintype "passive"))
      (node (ref "C11") (pin "2") (pinfunction "2_2") (pintype "passive"))
      (node (ref "C12") (pin "2") (pinfunction "2_2") (pintype "passive"))
      (node (ref "C13") (pin "2") (pinfunction "2_2") (pintype "passive"))
      (node (ref "C14") (pin "2") (pinfunction "2_2") (pintype "passive"))
      (node (ref "C15") (pin "2") (pinfunction "2_2") (pintype "passive"))
      (node (ref "C16") (pin "2") (pinfunction "2_2") (pintype "passive"))
      (node (ref "C17") (pin "2") (pinfunction "2_2") (pintype "passive"))
      (node (ref "C18") (pin "2") (pinfunction "2_2") (pintype "passive"))
      (node (ref "C19") (pin "2") (pinfunction "2_2") (pintype "passive"))
      (node (ref "C20") (pin "2") (pinfunction "2_2") (pintype "passive"))
      (node (ref "C21") (pin "2") (pinfunction "2_2") (pintype "passive"))
      (node (ref "C22") (pin "2") (pinfunction "2_2") (pintype "passive"))
      (node (ref "C23") (pin "2") (pinfunction "2_2") (pintype "passive"))
      (node (ref "C24") (pin "2") (pinfunction "2_2") (pintype "passive"))
      (node (ref "C25") (pin "2") (pinfunction "2_2") (pintype "passive"))
      (node (ref "C26") (pin "2") (pinfunction "2_2") (pintype "passive"))
      (node (ref "C27") (pin "2") (pinfunction "2_2") (pintype "passive"))
      (node (ref "C28") (pin "2") (pinfunction "2_2") (pintype "passive"))
      (node (ref "C29") (pin "1") (pinfunction "1_1") (pintype "passive"))
      (node (ref "C30") (pin "1") (pinfunction "1_1") (pintype "passive"))
      (node (ref "C31") (pin "2") (pinfunction "2_2") (pintype "passive"))
      (node (ref "C33") (pin "1") (pinfunction "1_1") (pintype "passive"))
      (node (ref "C34") (pin "2") (pinfunction "2_2") (pintype "passive"))
      (node (ref "C35") (pin "1") (pinfunction "1_1") (pintype "passive"))
      (node (ref "C36") (pin "2") (pinfunction "2_2") (pintype "passive"))
      (node (ref "C37") (pin "2") (pinfunction "2_2") (pintype "passive"))
      (node (ref "C39") (pin "2") (pinfunction "2_2") (pintype "passive"))
      (node (ref "C40") (pin "2") (pinfunction "2_2") (pintype "passive"))
      (node (ref "C41") (pin "2") (pinfunction "2_2") (pintype "passive"))
      (node (ref "C42") (pin "2") (pinfunction "2_2") (pintype "passive"))
      (node (ref "C43") (pin "1") (pinfunction "1_1") (pintype "passive"))
      (node (ref "C44") (pin "1") (pinfunction "1_1") (pintype "passive"))
      (node (ref "D10") (pin "2") (pinfunction "A_2") (pintype "passive"))
      (node (ref "IC10") (pin "B1") (pinfunction "MODE_B1") (pintype "input"))
      (node (ref "IC10") (pin "B2") (pinfunction "GND_B2") (pintype "power_in"))
      (node (ref "IC10") (pin "B3") (pinfunction "GND_B3") (pintype "power_in"))
      (node (ref "IC10") (pin "B4") (pinfunction "AGND_B4") (pintype "power_in"))
      (node (ref "IC10") (pin "C1") (pinfunction "GND_C1") (pintype "power_in"))
      (node (ref "IC10") (pin "C2") (pinfunction "GND_C2") (pintype "power_in"))
      (node (ref "IC10") (pin "C3") (pinfunction "GND_C3") (pintype "power_in"))
      (node (ref "IC10") (pin "C4") (pinfunction "GND_C4") (pintype "power_in"))
      (node (ref "IC11") (pin "B1") (pinfunction "MODE_B1") (pintype "input"))
      (node (ref "IC11") (pin "B2") (pinfunction "GND_B2") (pintype "power_in"))
      (node (ref "IC11") (pin "B3") (pinfunction "GND_B3") (pintype "power_in"))
      (node (ref "IC11") (pin "B4") (pinfunction "AGND_B4") (pintype "power_in"))
      (node (ref "IC11") (pin "C1") (pinfunction "GND_C1") (pintype "power_in"))
      (node (ref "IC11") (pin "C2") (pinfunction "GND_C2") (pintype "power_in"))
      (node (ref "IC11") (pin "C3") (pinfunction "GND_C3") (pintype "power_in"))
      (node (ref "IC11") (pin "C4") (pinfunction "GND_C4") (pintype "power_in"))
      (node (ref "IC12") (pin "B1") (pinfunction "MODE_B1") (pintype "input"))
      (node (ref "IC12") (pin "B2") (pinfunction "GND_B2") (pintype "power_in"))
      (node (ref "IC12") (pin "B3") (pinfunction "GND_B3") (pintype "power_in"))
      (node (ref "IC12") (pin "B4") (pinfunction "AGND_B4") (pintype "power_in"))
      (node (ref "IC12") (pin "C1") (pinfunction "GND_C1") (pintype "power_in"))
      (node (ref "IC12") (pin "C2") (pinfunction "GND_C2") (pintype "power_in"))
      (node (ref "IC12") (pin "C3") (pinfunction "GND_C3") (pintype "power_in"))
      (node (ref "IC12") (pin "C4") (pinfunction "GND_C4") (pintype "power_in"))
      (node (ref "IC13") (pin "B1") (pinfunction "MODE_B1") (pintype "input"))
      (node (ref "IC13") (pin "B2") (pinfunction "GND_B2") (pintype "power_in"))
      (node (ref "IC13") (pin "B3") (pinfunction "GND_B3") (pintype "power_in"))
      (node (ref "IC13") (pin "B4") (pinfunction "AGND_B4") (pintype "power_in"))
      (node (ref "IC13") (pin "C1") (pinfunction "GND_C1") (pintype "power_in"))
      (node (ref "IC13") (pin "C2") (pinfunction "GND_C2") (pintype "power_in"))
      (node (ref "IC13") (pin "C3") (pinfunction "GND_C3") (pintype "power_in"))
      (node (ref "IC13") (pin "C4") (pinfunction "GND_C4") (pintype "power_in"))
      (node (ref "IC14") (pin "B2") (pinfunction "GND_B2") (pintype "power_in"))
      (node (ref "IC15") (pin "1") (pinfunction "PGND_1") (pintype "power_in"))
      (node (ref "IC15") (pin "3") (pinfunction "AGND_3") (pintype "power_in"))
      (node (ref "IC16") (pin "11") (pinfunction "EP_11") (pintype "power_in"))
      (node (ref "IC16") (pin "4") (pinfunction "PGND_4") (pintype "power_in"))
      (node (ref "IC16") (pin "8") (pinfunction "GND_8") (pintype "power_in"))
      (node (ref "IC17") (pin "10") (pinfunction "-VDC_10") (pintype "power_in"))
      (node (ref "IC17") (pin "7") (pinfunction "-VDC_7") (pintype "power_in"))
      (node (ref "IC23") (pin "3") (pinfunction "E_3") (pintype "open_emitter"))
      (node (ref "J10") (pin "2") (pinfunction "2_2") (pintype "bidirectional"))
      (node (ref "J10") (pin "3") (pinfunction "3_3") (pintype "bidirectional"))
      (node (ref "LD10") (pin "1") (pinfunction "C_1") (pintype "passive"))
      (node (ref "LD11") (pin "1") (pinfunction "C_1") (pintype "passive"))
      (node (ref "LD12") (pin "1") (pinfunction "C_1") (pintype "passive"))
      (node (ref "R20") (pin "2") (pinfunction "2_2") (pintype "passive"))
      (node (ref "R21") (pin "2") (pinfunction "2_2") (pintype "passive"))
      (node (ref "R24") (pin "1") (pinfunction "1_1") (pintype "passive"))
      (node (ref "R31") (pin "2") (pinfunction "2_2") (pintype "passive"))
      (node (ref "R32") (pin "2") (pinfunction "2_2") (pintype "passive"))
      (node (ref "R34") (pin "2") (pinfunction "2_2") (pintype "passive"))
      (node (ref "R42") (pin "1") (pinfunction "1_1") (pintype "passive"))
      (node (ref "R43") (pin "1") (pinfunction "1_1") (pintype "passive"))
      (node (ref "R69") (pin "1") (pinfunction "1_1") (pintype "passive"))
      (node (ref "R70") (pin "1") (pinfunction "1_1") (pintype "passive"))
      (node (ref "T10") (pin "2") (pinfunction "S_2") (pintype "passive"))
      (node (ref "T11") (pin "2") (pinfunction "S_2") (pintype "passive"))
      (node (ref "T8") (pin "2") (pinfunction "S_2") (pintype "passive"))
    )
    (net (code "22") (name "Net-(B16-Pad1)") (class "Default")
      (node (ref "B16") (pin "1") (pinfunction "1_1") (pintype "bidirectional"))
      (node (ref "R69") (pin "2") (pinfunction "2_2") (pintype "passive"))
    )
    (net (code "23") (name "Net-(B17-Pad1)") (class "Default")
      (node (ref "B17") (pin "1") (pinfunction "1_1") (pintype "bidirectional"))
      (node (ref "R70") (pin "2") (pinfunction "2_2") (pintype "passive"))
    )
    (net (code "24") (name "Net-(C32-Pad1)") (class "Default")
      (node (ref "C32") (pin "1") (pinfunction "1_1") (pintype "passive"))
      (node (ref "R36") (pin "2") (pinfunction "2_2") (pintype "passive"))
    )
    (net (code "25") (name "Net-(C35-Pad2)") (class "Default")
      (node (ref "C35") (pin "2") (pinfunction "2_2") (pintype "passive"))
      (node (ref "R35") (pin "1") (pinfunction "1_1") (pintype "passive"))
    )
    (net (code "26") (name "Net-(C38-Pad2)") (class "Default")
      (node (ref "C38") (pin "2") (pinfunction "2_2") (pintype "passive"))
      (node (ref "L15") (pin "2") (pinfunction "2_2") (pintype "passive"))
      (node (ref "L16") (pin "1") (pinfunction "1_1") (pintype "passive"))
    )
    (net (code "27") (name "Net-(IC15-COMP)") (class "Default")
      (node (ref "IC15") (pin "5") (pinfunction "COMP_5") (pintype "input"))
      (node (ref "R35") (pin "2") (pinfunction "2_2") (pintype "passive"))
    )
    (net (code "28") (name "Net-(IC15-FB)") (class "Default")
      (node (ref "IC15") (pin "4") (pinfunction "FB_4") (pintype "input"))
      (node (ref "R33") (pin "1") (pinfunction "1_1") (pintype "passive"))
      (node (ref "R34") (pin "1") (pinfunction "1_1") (pintype "passive"))
      (node (ref "R36") (pin "1") (pinfunction "1_1") (pintype "passive"))
    )
    (net (code "29") (name "Net-(IC15-VSW)") (class "Default")
      (node (ref "IC15") (pin "8") (pinfunction "VSW_8") (pintype "output"))
      (node (ref "L14") (pin "1") (pinfunction "1_1") (pintype "passive"))
    )
    (net (code "30") (name "Net-(IC17-AT-DET)") (class "Default")
      (node (ref "IC17") (pin "3") (pinfunction "AT-DET_3") (pintype "input"))
      (node (ref "IC23") (pin "2") (pinfunction "C_2") (pintype "input"))
    )
    (net (code "31") (name "Net-(IC17-VIN+)") (class "Default")
      (node (ref "IC17") (pin "1") (pinfunction "VIN+_1") (pintype "input"))
      (node (ref "R38") (pin "2") (pinfunction "2_2") (pintype "passive"))
      (node (ref "R39") (pin "2") (pinfunction "2_2") (pintype "passive"))
    )
    (net (code "32") (name "Net-(IC17-VIN-)") (class "Default")
      (node (ref "C44") (pin "2") (pinfunction "2_2") (pintype "passive"))
      (node (ref "IC17") (pin "2") (pinfunction "VIN-_2") (pintype "output"))
      (node (ref "L16") (pin "3") (pinfunction "3_3") (pintype "passive"))
    )
    (net (code "33") (name "Net-(IC18-A)") (class "Default")
      (node (ref "IC18") (pin "1") (pinfunction "A_1") (pintype "input"))
      (node (ref "R168") (pin "1") (pinfunction "1_1") (pintype "passive"))
    )
    (net (code "34") (name "Net-(IC18-C-Pad4)") (class "Default")
      (node (ref "IC18") (pin "4") (pinfunction "C_4") (pintype "open_collector"))
      (node (ref "R140") (pin "1") (pinfunction "1_1") (pintype "passive"))
      (node (ref "R146") (pin "2") (pinfunction "2_2") (pintype "passive"))
    )
    (net (code "35") (name "Net-(IC18-E)") (class "Default")
      (node (ref "C136") (pin "2") (pinfunction "2_2") (pintype "passive"))
      (node (ref "IC18") (pin "3") (pinfunction "E_3") (pintype "open_emitter"))
      (node (ref "R184") (pin "2") (pinfunction "2_2") (pintype "passive"))
      (node (ref "T7") (pin "1") (pinfunction "G_1") (pintype "passive"))
    )
    (net (code "36") (name "Net-(IC23-A)") (class "Default")
      (node (ref "C43") (pin "2") (pinfunction "2_2") (pintype "passive"))
      (node (ref "IC23") (pin "1") (pinfunction "A_1") (pintype "input"))
      (node (ref "L16") (pin "4") (pinfunction "4_4") (pintype "passive"))
      (node (ref "R38") (pin "1") (pinfunction "1_1") (pintype "passive"))
      (node (ref "R39") (pin "1") (pinfunction "1_1") (pintype "passive"))
    )
    (net (code "37") (name "Net-(LD10-A)") (class "Default")
      (node (ref "LD10") (pin "2") (pinfunction "A_2") (pintype "passive"))
      (node (ref "R10") (pin "1") (pinfunction "1_1") (pintype "passive"))
    )
    (net (code "38") (name "Net-(LD11-A)") (class "Default")
      (node (ref "LD11") (pin "2") (pinfunction "A_2") (pintype "passive"))
      (node (ref "R11") (pin "2") (pinfunction "2_2") (pintype "passive"))
    )
    (net (code "39") (name "Net-(LD12-A)") (class "Default")
      (node (ref "LD12") (pin "2") (pinfunction "A_2") (pintype "passive"))
      (node (ref "R13") (pin "2") (pinfunction "2_2") (pintype "passive"))
    )
    (net (code "40") (name "Net-(LD13-A)") (class "Default")
      (node (ref "LD13") (pin "2") (pinfunction "A_2") (pintype "passive"))
      (node (ref "R15") (pin "2") (pinfunction "2_2") (pintype "passive"))
    )
    (net (code "41") (name "Net-(LD13-C)") (class "Default")
      (node (ref "LD13") (pin "1") (pinfunction "C_1") (pintype "passive"))
      (node (ref "T10") (pin "3") (pinfunction "D_3") (pintype "passive"))
    )
    (net (code "42") (name "Net-(LD14-A)") (class "Default")
      (node (ref "LD14") (pin "2") (pinfunction "A_2") (pintype "passive"))
      (node (ref "R22") (pin "2") (pinfunction "2_2") (pintype "passive"))
    )
    (net (code "43") (name "Net-(LD14-C)") (class "Default")
      (node (ref "LD14") (pin "1") (pinfunction "C_1") (pintype "passive"))
      (node (ref "T11") (pin "3") (pinfunction "D_3") (pintype "passive"))
    )
    (net (code "44") (name "Net-(T7-D)") (class "Default")
      (node (ref "C156") (pin "1") (pinfunction "1_1") (pintype "passive"))
      (node (ref "C38") (pin "1") (pinfunction "1_1") (pintype "passive"))
      (node (ref "L16") (pin "2") (pinfunction "2_2") (pintype "passive"))
      (node (ref "R166") (pin "2") (pinfunction "2_2") (pintype "passive"))
      (node (ref "T7") (pin "3") (pinfunction "D_3") (pintype "passive"))
    )
    (net (code "45") (name "Net-(T8-D)") (class "Default")
      (node (ref "IC18") (pin "2") (pinfunction "C_2") (pintype "input"))
      (node (ref "T8") (pin "3") (pinfunction "D_3") (pintype "passive"))
    )
    (net (code "46") (name "Net-(T11-G)") (class "Default")
      (node (ref "R23") (pin "1") (pinfunction "1_1") (pintype "passive"))
      (node (ref "R24") (pin "2") (pinfunction "2_2") (pintype "passive"))
      (node (ref "T11") (pin "1") (pinfunction "G_1") (pintype "passive"))
    )
    (net (code "47") (name "Net-(T13A-B)") (class "Default")
      (node (ref "R40") (pin "1") (pinfunction "1_1") (pintype "passive"))
      (node (ref "T13") (pin "2") (pinfunction "B_2") (pintype "passive"))
    )
    (net (code "48") (name "Net-(T13A-C)") (class "Default")
      (node (ref "R42") (pin "2") (pinfunction "2_2") (pintype "passive"))
      (node (ref "T12") (pin "4") (pinfunction "S_4") (pintype "passive"))
      (node (ref "T13") (pin "6") (pinfunction "C_6") (pintype "passive"))
    )
    (net (code "49") (name "Net-(T13B-B)") (class "Default")
      (node (ref "R40") (pin "2") (pinfunction "2_2") (pintype "passive"))
      (node (ref "R43") (pin "2") (pinfunction "2_2") (pintype "passive"))
      (node (ref "T13") (pin "3") (pinfunction "C_3") (pintype "passive"))
      (node (ref "T13") (pin "5") (pinfunction "B_5") (pintype "passive"))
    )
    (net (code "50") (name "P1.2VTT") (class "Default")
      (node (ref "C27") (pin "1") (pinfunction "1_1") (pintype "passive"))
      (node (ref "IC14") (pin "A2") (pinfunction "OUT_A2") (pintype "power_in"))
      (node (ref "TP15") (pin "1") (pinfunction "1_1") (pintype "bidirectional"))
    )
    (net (code "51") (name "P1V0") (class "Default")
      (node (ref "C14") (pin "1") (pinfunction "1_1") (pintype "passive"))
      (node (ref "C15") (pin "1") (pinfunction "1_1") (pintype "passive"))
      (node (ref "IC10") (pin "A4") (pinfunction "VOUT_A4") (pintype "passive"))
      (node (ref "L10") (pin "2") (pinfunction "2_2") (pintype "passive"))
      (node (ref "R14") (pin "1") (pinfunction "1_1") (pintype "passive"))
      (node (ref "R14") (pin "2") (pinfunction "2_2") (pintype "passive"))
      (node (ref "R17") (pin "2") (pinfunction "2_2") (pintype "passive"))
      (node (ref "T10") (pin "1") (pinfunction "G_1") (pintype "passive"))
      (node (ref "TP13") (pin "1") (pinfunction "1_1") (pintype "bidirectional"))
    )
    (net (code "52") (name "P1V5") (class "Default")
      (node (ref "C22") (pin "1") (pinfunction "1_1") (pintype "passive"))
      (node (ref "C23") (pin "1") (pinfunction "1_1") (pintype "passive"))
      (node (ref "IC12") (pin "A4") (pinfunction "VOUT_A4") (pintype "passive"))
      (node (ref "IC16") (pin "1") (pinfunction "VDDQSNS_1") (pintype "input"))
      (node (ref "L12") (pin "2") (pinfunction "2_2") (pintype "passive"))
      (node (ref "R28") (pin "2") (pinfunction "2_2") (pintype "passive"))
      (node (ref "R37") (pin "2") (pinfunction "2_2") (pintype "passive"))
    )
    (net (code "53") (name "P1V8") (class "Default")
      (node (ref "C16") (pin "1") (pinfunction "1_1") (pintype "passive"))
      (node (ref "C17") (pin "1") (pinfunction "1_1") (pintype "passive"))
      (node (ref "IC11") (pin "A4") (pinfunction "VOUT_A4") (pintype "passive"))
      (node (ref "L11") (pin "2") (pinfunction "2_2") (pintype "passive"))
      (node (ref "R18") (pin "2") (pinfunction "2_2") (pintype "passive"))
      (node (ref "R23") (pin "2") (pinfunction "2_2") (pintype "passive"))
      (node (ref "TP14") (pin "1") (pinfunction "1_1") (pintype "bidirectional"))
    )
    (net (code "54") (name "P3V3") (class "Default")
      (node (ref "C24") (pin "1") (pinfunction "1_1") (pintype "passive"))
      (node (ref "C25") (pin "1") (pinfunction "1_1") (pintype "passive"))
      (node (ref "C42") (pin "1") (pinfunction "1_1") (pintype "passive"))
      (node (ref "IC13") (pin "A4") (pinfunction "VOUT_A4") (pintype "passive"))
      (node (ref "IC16") (pin "10") (pinfunction "VDD_10") (pintype "power_in"))
      (node (ref "L13") (pin "2") (pinfunction "2_2") (pintype "passive"))
      (node (ref "R11") (pin "1") (pinfunction "1_1") (pintype "passive"))
      (node (ref "R15") (pin "1") (pinfunction "1_1") (pintype "passive"))
      (node (ref "R168") (pin "2") (pinfunction "2_2") (pintype "passive"))
      (node (ref "R22") (pin "1") (pinfunction "1_1") (pintype "passive"))
      (node (ref "R27") (pin "2") (pinfunction "2_2") (pintype "passive"))
      (node (ref "R29") (pin "2") (pinfunction "2_2") (pintype "passive"))
      (node (ref "R30") (pin "2") (pinfunction "2_2") (pintype "passive"))
      (node (ref "R41") (pin "2") (pinfunction "2_2") (pintype "passive"))
      (node (ref "TP11") (pin "1") (pinfunction "1_1") (pintype "bidirectional"))
    )
    (net (code "55") (name "P5V0") (class "Default")
      (node (ref "C10") (pin "1") (pinfunction "1_1") (pintype "passive"))
      (node (ref "C11") (pin "1") (pinfunction "1_1") (pintype "passive"))
      (node (ref "C32") (pin "2") (pinfunction "2_2") (pintype "passive"))
      (node (ref "C33") (pin "2") (pinfunction "2_2") (pintype "passive"))
      (node (ref "IC10") (pin "A2") (pinfunction "EN_A2") (pintype "input"))
      (node (ref "IC10") (pin "D1") (pinfunction "VIN_D1") (pintype "power_in"))
      (node (ref "IC10") (pin "D2") (pinfunction "VIN_D2") (pintype "power_in"))
      (node (ref "IC10") (pin "E1") (pinfunction "VIN_E1") (pintype "power_in"))
      (node (ref "IC10") (pin "E2") (pinfunction "VIN_E2") (pintype "power_in"))
      (node (ref "L14") (pin "2") (pinfunction "2_2") (pintype "passive"))
      (node (ref "R12") (pin "1") (pinfunction "1_1") (pintype "passive"))
      (node (ref "R13") (pin "1") (pinfunction "1_1") (pintype "passive"))
      (node (ref "R19") (pin "2") (pinfunction "2_2") (pintype "passive"))
      (node (ref "R25") (pin "1") (pinfunction "1_1") (pintype "passive"))
      (node (ref "R26") (pin "1") (pinfunction "1_1") (pintype "passive"))
      (node (ref "R33") (pin "2") (pinfunction "2_2") (pintype "passive"))
      (node (ref "TP12") (pin "1") (pinfunction "1_1") (pintype "bidirectional"))
    )
    (net (code "56") (name "P12V0") (class "Default")
      (node (ref "C28") (pin "1") (pinfunction "1_1") (pintype "passive"))
      (node (ref "C29") (pin "2") (pinfunction "2_2") (pintype "passive"))
      (node (ref "C30") (pin "2") (pinfunction "2_2") (pintype "passive"))
      (node (ref "C31") (pin "1") (pinfunction "1_1") (pintype "passive"))
      (node (ref "C34") (pin "1") (pinfunction "1_1") (pintype "passive"))
      (node (ref "D10") (pin "1") (pinfunction "C_1") (pintype "passive"))
      (node (ref "IC15") (pin "2") (pinfunction "VIN_2") (pintype "input"))
      (node (ref "IC15") (pin "6") (pinfunction "EN_6") (pintype "input"))
      (node (ref "J10") (pin "1") (pinfunction "1_1") (pintype "bidirectional"))
      (node (ref "R10") (pin "2") (pinfunction "2_2") (pintype "passive"))
      (node (ref "T12") (pin "1") (pinfunction "S_1") (pintype "passive"))
      (node (ref "T12") (pin "2") (pinfunction "S_2") (pintype "passive"))
      (node (ref "T12") (pin "3") (pinfunction "S_3") (pintype "passive"))
      (node (ref "T13") (pin "1") (pinfunction "E_1") (pintype "passive"))
      (node (ref "TP10") (pin "1") (pinfunction "1_1") (pintype "bidirectional"))
    )
    (net (code "57") (name "VTT") (class "Default")
      (node (ref "C37") (pin "1") (pinfunction "1_1") (pintype "passive"))
      (node (ref "IC16") (pin "3") (pinfunction "VTT_3") (pintype "output"))
      (node (ref "IC16") (pin "5") (pinfunction "VTTSNS_5") (pintype "input"))
    )
    (net (code "58") (name "VTT_REF") (class "Default")
      (node (ref "C39") (pin "1") (pinfunction "1_1") (pintype "passive"))
      (node (ref "IC16") (pin "6") (pinfunction "VTTREF_6") (pintype "output"))
    )
    (net (code "59") (name "unconnected-(IC17-ADJ-Pad9)") (class "Default")
      (node (ref "IC17") (pin "9") (pinfunction "ADJ_9") (pintype "input+no_connect"))
    )
  )
)
